# EAGLE-Piclodio3.net
KiCad netlist of a schematic drawn in EAGLE
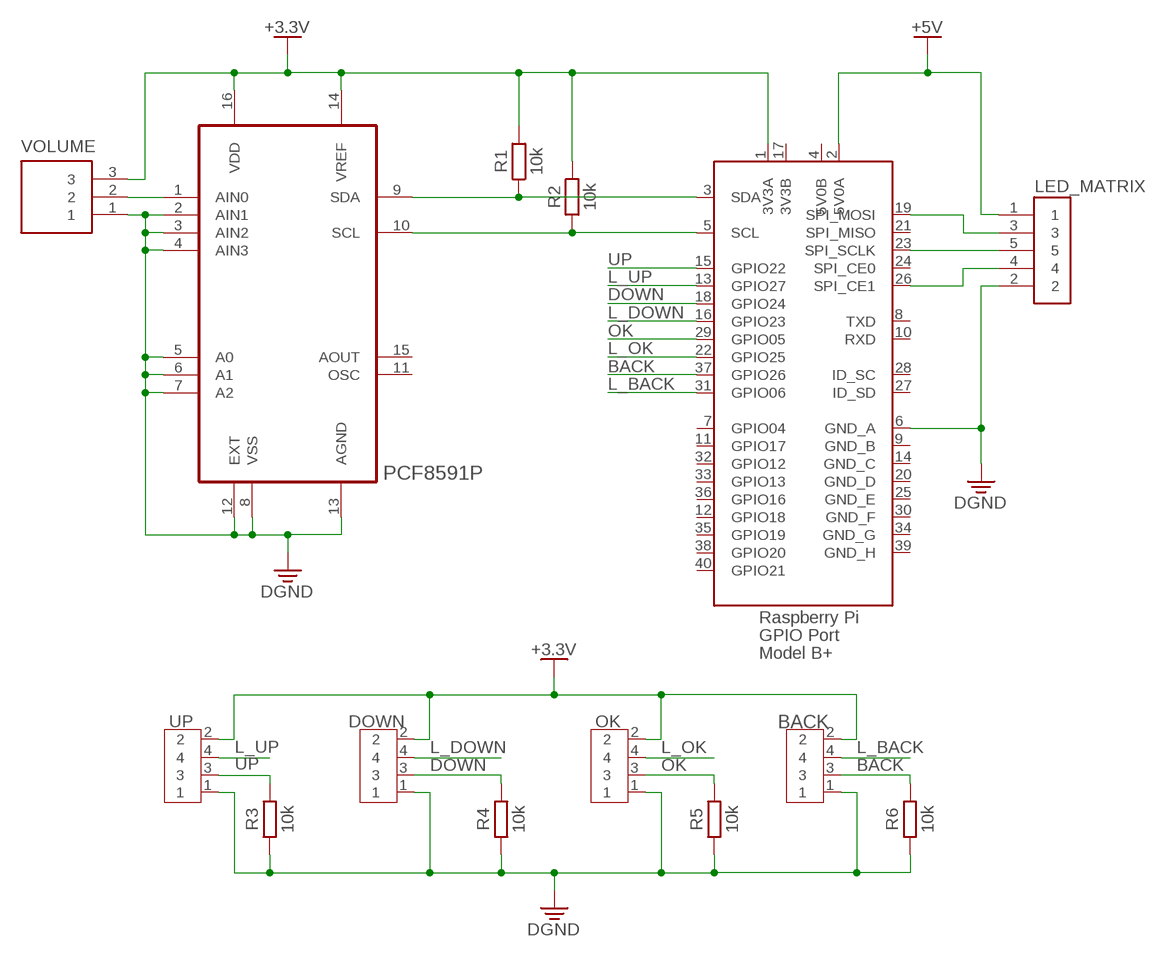
[diagram p0: schematic, sheet 1]

(export (version "E")
  (design (tool "Eeschema 10.0.6"))
  (components
    (comp (ref "BACK")
      (value "3A/250V")
      (footprint "eagle-import:B4B-XH-A")
      (fields (field (name "MANUFACTURER") "JST (XH connector)") (field (name "MPN") "B4B-XH-A"))
      (libsource (lib "eagle-import") (part "B4B-XH-A"))
    )
    (comp (ref "DOWN")
      (value "3A/250V")
      (footprint "eagle-import:B4B-XH-A")
      (fields (field (name "MANUFACTURER") "JST (XH connector)") (field (name "MPN") "B4B-XH-A"))
      (libsource (lib "eagle-import") (part "B4B-XH-A"))
    )
    (comp (ref "LED_MATRIX")
      (value "S5B-XH-A(LF)(SN)")
      (footprint "eagle-import:JST_S5B-XH-A(LF)(SN)")
      (fields (field (name "MANUFACTURER") "JST"))
      (libsource (lib "eagle-import") (part "S5B-XH-A(LF)(SN)"))
    )
    (comp (ref "OK")
      (value "3A/250V")
      (footprint "eagle-import:B4B-XH-A")
      (fields (field (name "MANUFACTURER") "JST (XH connector)") (field (name "MPN") "B4B-XH-A"))
      (libsource (lib "eagle-import") (part "B4B-XH-A"))
    )
    (comp (ref "R1")
      (value "10k")
      (footprint "eagle-import:RESAD1176W63L850D250B")
      (libsource (lib "eagle-import") (part "RAXIAL-11.7MM-PITCH_"))
    )
    (comp (ref "R2")
      (value "10k")
      (footprint "eagle-import:RESAD1176W63L850D250B")
      (libsource (lib "eagle-import") (part "RAXIAL-11.7MM-PITCH_"))
    )
    (comp (ref "R3")
      (value "10k")
      (footprint "eagle-import:RESAD1176W63L850D250B")
      (libsource (lib "eagle-import") (part "RAXIAL-11.7MM-PITCH_"))
    )
    (comp (ref "R4")
      (value "10k")
      (footprint "eagle-import:RESAD1176W63L850D250B")
      (libsource (lib "eagle-import") (part "RAXIAL-11.7MM-PITCH_"))
    )
    (comp (ref "R5")
      (value "10k")
      (footprint "eagle-import:RESAD1176W63L850D250B")
      (libsource (lib "eagle-import") (part "RAXIAL-11.7MM-PITCH_"))
    )
    (comp (ref "R6")
      (value "10k")
      (footprint "eagle-import:RESAD1176W63L850D250B")
      (libsource (lib "eagle-import") (part "RAXIAL-11.7MM-PITCH_"))
    )
    (comp (ref "U2")
      (value "PCF8591P")
      (footprint "eagle-import:DIP254P762X420-16")
      (fields (field (name "MF") "NXP USA"))
      (libsource (lib "eagle-import") (part "PCF8591P"))
    )
    (comp (ref "UP")
      (value "3A/250V")
      (footprint "eagle-import:B4B-XH-A")
      (fields
        (field (name "MANUFACTURER") "JST (XH connector)")
        (field (name "MPN") "B4B-XH-A")
        (field (name "SPICEPREFIX") "E")
      )
      (libsource (lib "eagle-import") (part "B4B-XH-A"))
    )
    (comp (ref "VOLUME")
      (value "S3B-XH-A(LF)(SN)")
      (footprint "eagle-import:JST_S3B-XH-A(LF)(SN)")
      (fields (field (name "MANUFACTURER") "JST"))
      (libsource (lib "eagle-import") (part "S3B-XH-A(LF)(SN)"))
    )
    (comp (ref "X1")
      (value "RASPI_BOARD_B+#_H")
      (footprint "eagle-import:RASPI_BOARD_B+HAT")
      (libsource (lib "eagle-import") (part "RASPI_BOARD_B+#_H"))
    )
  )
  (nets
    (net (code "1") (name "+3.3V") (class "Default")
      (node (ref "BACK") (pin "2") (pinfunction "2_2") (pintype "bidirectional"))
      (node (ref "DOWN") (pin "2") (pinfunction "2_2") (pintype "bidirectional"))
      (node (ref "OK") (pin "2") (pinfunction "2_2") (pintype "bidirectional"))
      (node (ref "R1") (pin "2") (pinfunction "2_2") (pintype "passive"))
      (node (ref "R2") (pin "1") (pinfunction "1_1") (pintype "passive"))
      (node (ref "U2") (pin "14") (pinfunction "VREF_14") (pintype "input"))
      (node (ref "U2") (pin "16") (pinfunction "VDD_16") (pintype "power_in"))
      (node (ref "UP") (pin "2") (pinfunction "2_2") (pintype "bidirectional"))
      (node (ref "VOLUME") (pin "3") (pinfunction "3_3") (pintype "passive"))
      (node (ref "X1") (pin "1") (pinfunction "3V3A_1") (pintype "power_in"))
    )
    (net (code "2") (name "+5V") (class "Default")
      (node (ref "LED_MATRIX") (pin "1") (pinfunction "1_1") (pintype "passive"))
      (node (ref "X1") (pin "2") (pinfunction "5V0A_2") (pintype "power_in"))
    )
    (net (code "3") (name "/BACK") (class "Default")
      (node (ref "BACK") (pin "3") (pinfunction "3_3") (pintype "bidirectional"))
      (node (ref "R6") (pin "2") (pinfunction "2_2") (pintype "passive"))
      (node (ref "X1") (pin "37") (pinfunction "GPIO26_37") (pintype "input"))
    )
    (net (code "4") (name "/DOWN") (class "Default")
      (node (ref "DOWN") (pin "3") (pinfunction "3_3") (pintype "bidirectional"))
      (node (ref "R4") (pin "2") (pinfunction "2_2") (pintype "passive"))
      (node (ref "X1") (pin "18") (pinfunction "GPIO24_18") (pintype "input"))
    )
    (net (code "5") (name "/L_BACK") (class "Default")
      (node (ref "BACK") (pin "4") (pinfunction "4_4") (pintype "bidirectional"))
      (node (ref "X1") (pin "31") (pinfunction "GPIO06_31") (pintype "output"))
    )
    (net (code "6") (name "/L_DOWN") (class "Default")
      (node (ref "DOWN") (pin "4") (pinfunction "4_4") (pintype "bidirectional"))
      (node (ref "X1") (pin "16") (pinfunction "GPIO23_16") (pintype "output"))
    )
    (net (code "7") (name "/L_OK") (class "Default")
      (node (ref "OK") (pin "4") (pinfunction "4_4") (pintype "bidirectional"))
      (node (ref "X1") (pin "22") (pinfunction "GPIO25_22") (pintype "output"))
    )
    (net (code "8") (name "/L_UP") (class "Default")
      (node (ref "UP") (pin "4") (pinfunction "4_4") (pintype "bidirectional"))
      (node (ref "X1") (pin "13") (pinfunction "GPIO27_13") (pintype "output"))
    )
    (net (code "9") (name "/OK") (class "Default")
      (node (ref "OK") (pin "3") (pinfunction "3_3") (pintype "bidirectional"))
      (node (ref "R5") (pin "2") (pinfunction "2_2") (pintype "passive"))
      (node (ref "X1") (pin "29") (pinfunction "GPIO05_29") (pintype "input"))
    )
    (net (code "10") (name "/UP") (class "Default")
      (node (ref "R3") (pin "2") (pinfunction "2_2") (pintype "passive"))
      (node (ref "UP") (pin "3") (pinfunction "3_3") (pintype "bidirectional"))
      (node (ref "X1") (pin "15") (pinfunction "GPIO22_15") (pintype "input"))
    )
    (net (code "11") (name "DGND") (class "Default")
      (node (ref "BACK") (pin "1") (pinfunction "1_1") (pintype "bidirectional"))
      (node (ref "DOWN") (pin "1") (pinfunction "1_1") (pintype "bidirectional"))
      (node (ref "LED_MATRIX") (pin "2") (pinfunction "2_2") (pintype "passive"))
      (node (ref "OK") (pin "1") (pinfunction "1_1") (pintype "bidirectional"))
      (node (ref "R3") (pin "1") (pinfunction "1_1") (pintype "passive"))
      (node (ref "R4") (pin "1") (pinfunction "1_1") (pintype "passive"))
      (node (ref "R5") (pin "1") (pinfunction "1_1") (pintype "passive"))
      (node (ref "R6") (pin "1") (pinfunction "1_1") (pintype "passive"))
      (node (ref "U2") (pin "12") (pinfunction "EXT_12") (pintype "input"))
      (node (ref "U2") (pin "13") (pinfunction "AGND_13") (pintype "power_in"))
      (node (ref "U2") (pin "2") (pinfunction "AIN1_2") (pintype "input"))
      (node (ref "U2") (pin "3") (pinfunction "AIN2_3") (pintype "input"))
      (node (ref "U2") (pin "4") (pinfunction "AIN3_4") (pintype "input"))
      (node (ref "U2") (pin "5") (pinfunction "A0_5") (pintype "input"))
      (node (ref "U2") (pin "6") (pinfunction "A1_6") (pintype "input"))
      (node (ref "U2") (pin "7") (pinfunction "A2_7") (pintype "input"))
      (node (ref "U2") (pin "8") (pinfunction "VSS_8") (pintype "input"))
      (node (ref "UP") (pin "1") (pinfunction "1_1") (pintype "bidirectional"))
      (node (ref "VOLUME") (pin "1") (pinfunction "1_1") (pintype "passive"))
      (node (ref "X1") (pin "6") (pinfunction "GND_A_6") (pintype "power_in"))
    )
    (net (code "12") (name "Net-(U2-AIN0)") (class "Default")
      (node (ref "U2") (pin "1") (pinfunction "AIN0_1") (pintype "input"))
      (node (ref "VOLUME") (pin "2") (pinfunction "2_2") (pintype "passive"))
    )
    (net (code "13") (name "Net-(U2-SCL)") (class "Default")
      (node (ref "R2") (pin "2") (pinfunction "2_2") (pintype "passive"))
      (node (ref "U2") (pin "10") (pinfunction "SCL_10") (pintype "input"))
      (node (ref "X1") (pin "5") (pinfunction "SCL_5") (pintype "bidirectional"))
    )
    (net (code "14") (name "Net-(U2-SDA)") (class "Default")
      (node (ref "R1") (pin "1") (pinfunction "1_1") (pintype "passive"))
      (node (ref "U2") (pin "9") (pinfunction "SDA_9") (pintype "bidirectional"))
      (node (ref "X1") (pin "3") (pinfunction "SDA_3") (pintype "bidirectional"))
    )
    (net (code "15") (name "Net-(X1-SPI_CE1)") (class "Default")
      (node (ref "LED_MATRIX") (pin "4") (pinfunction "4_4") (pintype "passive"))
      (node (ref "X1") (pin "26") (pinfunction "SPI_CE1_26") (pintype "bidirectional"))
    )
    (net (code "16") (name "Net-(X1-SPI_MOSI)") (class "Default")
      (node (ref "LED_MATRIX") (pin "3") (pinfunction "3_3") (pintype "passive"))
      (node (ref "X1") (pin "19") (pinfunction "SPI_MOSI_19") (pintype "bidirectional"))
    )
    (net (code "17") (name "Net-(X1-SPI_SCLK)") (class "Default")
      (node (ref "LED_MATRIX") (pin "5") (pinfunction "5_5") (pintype "passive"))
      (node (ref "X1") (pin "23") (pinfunction "SPI_SCLK_23") (pintype "bidirectional"))
    )
    (net (code "18") (name "unconnected-(U2-AOUT-Pad15)") (class "Default")
      (node (ref "U2") (pin "15") (pinfunction "AOUT_15") (pintype "output"))
    )
    (net (code "19") (name "unconnected-(U2-OSC-Pad11)") (class "Default")
      (node (ref "U2") (pin "11") (pinfunction "OSC_11") (pintype "bidirectional"))
    )
    (net (code "20") (name "unconnected-(X1-3V3B-Pad17)") (class "Default")
      (node (ref "X1") (pin "17") (pinfunction "3V3B_17") (pintype "no_connect"))
    )
    (net (code "21") (name "unconnected-(X1-5V0B-Pad4)") (class "Default")
      (node (ref "X1") (pin "4") (pinfunction "5V0B_4") (pintype "no_connect"))
    )
    (net (code "22") (name "unconnected-(X1-GND_B-Pad9)") (class "Default")
      (node (ref "X1") (pin "9") (pinfunction "GND_B_9") (pintype "no_connect"))
    )
    (net (code "23") (name "unconnected-(X1-GND_C-Pad14)") (class "Default")
      (node (ref "X1") (pin "14") (pinfunction "GND_C_14") (pintype "no_connect"))
    )
    (net (code "24") (name "unconnected-(X1-GND_D-Pad20)") (class "Default")
      (node (ref "X1") (pin "20") (pinfunction "GND_D_20") (pintype "no_connect"))
    )
    (net (code "25") (name "unconnected-(X1-GND_E-Pad25)") (class "Default")
      (node (ref "X1") (pin "25") (pinfunction "GND_E_25") (pintype "no_connect"))
    )
    (net (code "26") (name "unconnected-(X1-GND_F-Pad30)") (class "Default")
      (node (ref "X1") (pin "30") (pinfunction "GND_F_30") (pintype "no_connect"))
    )
    (net (code "27") (name "unconnected-(X1-GND_G-Pad34)") (class "Default")
      (node (ref "X1") (pin "34") (pinfunction "GND_G_34") (pintype "no_connect"))
    )
    (net (code "28") (name "unconnected-(X1-GND_H-Pad39)") (class "Default")
      (node (ref "X1") (pin "39") (pinfunction "GND_H_39") (pintype "no_connect"))
    )
    (net (code "29") (name "unconnected-(X1-GPIO04-Pad7)") (class "Default")
      (node (ref "X1") (pin "7") (pinfunction "GPIO04_7") (pintype "no_connect"))
    )
    (net (code "30") (name "unconnected-(X1-GPIO12-Pad32)") (class "Default")
      (node (ref "X1") (pin "32") (pinfunction "GPIO12_32") (pintype "no_connect"))
    )
    (net (code "31") (name "unconnected-(X1-GPIO13-Pad33)") (class "Default")
      (node (ref "X1") (pin "33") (pinfunction "GPIO13_33") (pintype "no_connect"))
    )
    (net (code "32") (name "unconnected-(X1-GPIO16-Pad36)") (class "Default")
      (node (ref "X1") (pin "36") (pinfunction "GPIO16_36") (pintype "no_connect"))
    )
    (net (code "33") (name "unconnected-(X1-GPIO17-Pad11)") (class "Default")
      (node (ref "X1") (pin "11") (pinfunction "GPIO17_11") (pintype "no_connect"))
    )
    (net (code "34") (name "unconnected-(X1-GPIO18-Pad12)") (class "Default")
      (node (ref "X1") (pin "12") (pinfunction "GPIO18_12") (pintype "no_connect"))
    )
    (net (code "35") (name "unconnected-(X1-GPIO19-Pad35)") (class "Default")
      (node (ref "X1") (pin "35") (pinfunction "GPIO19_35") (pintype "no_connect"))
    )
    (net (code "36") (name "unconnected-(X1-GPIO20-Pad38)") (class "Default")
      (node (ref "X1") (pin "38") (pinfunction "GPIO20_38") (pintype "no_connect"))
    )
    (net (code "37") (name "unconnected-(X1-GPIO21-Pad40)") (class "Default")
      (node (ref "X1") (pin "40") (pinfunction "GPIO21_40") (pintype "no_connect"))
    )
    (net (code "38") (name "unconnected-(X1-ID_SC-Pad28)") (class "Default")
      (node (ref "X1") (pin "28") (pinfunction "ID_SC_28") (pintype "no_connect"))
    )
    (net (code "39") (name "unconnected-(X1-ID_SD-Pad27)") (class "Default")
      (node (ref "X1") (pin "27") (pinfunction "ID_SD_27") (pintype "no_connect"))
    )
    (net (code "40") (name "unconnected-(X1-RXD-Pad10)") (class "Default")
      (node (ref "X1") (pin "10") (pinfunction "RXD_10") (pintype "no_connect"))
    )
    (net (code "41") (name "unconnected-(X1-SPI_CE0-Pad24)") (class "Default")
      (node (ref "X1") (pin "24") (pinfunction "SPI_CE0_24") (pintype "no_connect"))
    )
    (net (code "42") (name "unconnected-(X1-SPI_MISO-Pad21)") (class "Default")
      (node (ref "X1") (pin "21") (pinfunction "SPI_MISO_21") (pintype "bidirectional"))
    )
    (net (code "43") (name "unconnected-(X1-TXD-Pad8)") (class "Default")
      (node (ref "X1") (pin "8") (pinfunction "TXD_8") (pintype "no_connect"))
    )
  )
)
